# zxdos_trainer.net
KiCad netlist of a schematic drawn in EAGLE
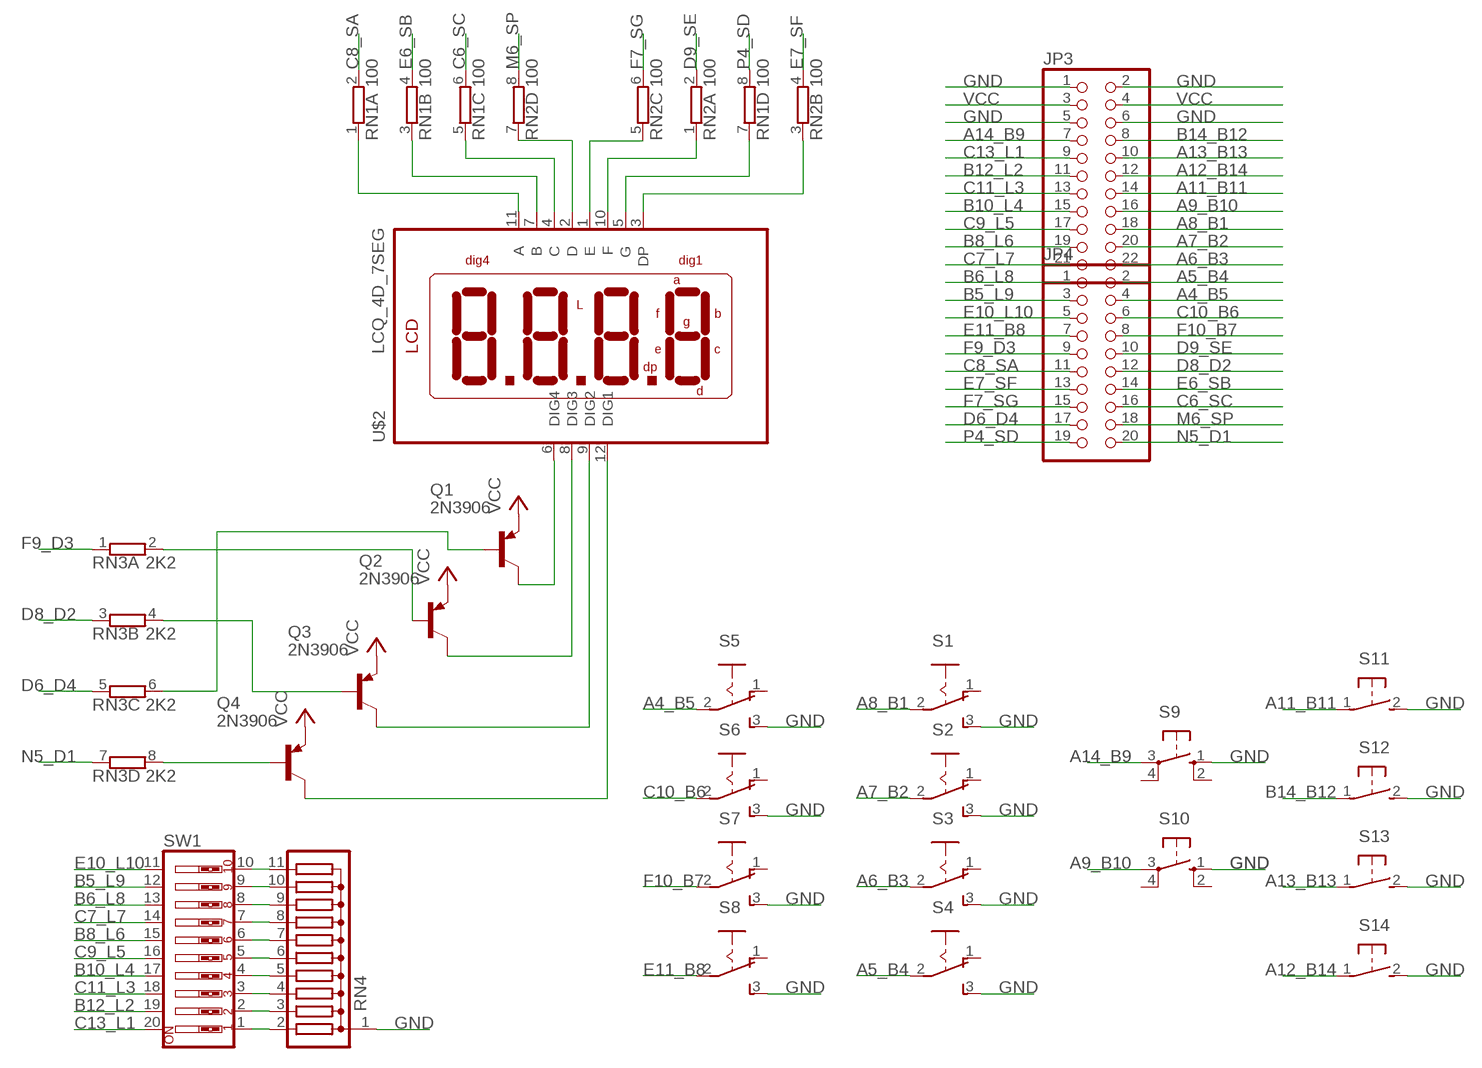
[diagram p0: schematic, sheet 1]

(export (version "E")
  (design (tool "Eeschema 10.0.6"))
  (components
    (comp (ref "JP3")
      (value "PINHD-2X11")
      (footprint "eagle-import:2X11")
      (libsource (lib "eagle-import") (part "PINHD-2X11"))
    )
    (comp (ref "JP4")
      (value "PINHD-2X10")
      (footprint "eagle-import:2X10")
      (libsource (lib "eagle-import") (part "PINHD-2X10"))
    )
    (comp (ref "Q1")
      (value "2N3906")
      (footprint "eagle-import:TO92")
      (libsource (lib "eagle-import") (part "2N3906"))
    )
    (comp (ref "Q2")
      (value "2N3906")
      (footprint "eagle-import:TO92")
      (libsource (lib "eagle-import") (part "2N3906"))
    )
    (comp (ref "Q3")
      (value "2N3906")
      (footprint "eagle-import:TO92")
      (libsource (lib "eagle-import") (part "2N3906"))
    )
    (comp (ref "Q4")
      (value "2N3906")
      (footprint "eagle-import:TO92")
      (libsource (lib "eagle-import") (part "2N3906"))
    )
    (comp (ref "RN1")
      (value "100")
      (footprint "eagle-import:SIL8")
      (libsource (lib "eagle-import") (part "E4R"))
    )
    (comp (ref "RN2")
      (value "100")
      (footprint "eagle-import:SIL8")
      (libsource (lib "eagle-import") (part "E4R"))
    )
    (comp (ref "RN3")
      (value "2K2")
      (footprint "eagle-import:SIL8")
      (libsource (lib "eagle-import") (part "E4R"))
    )
    (comp (ref "RN4")
      (value "G10R")
      (footprint "eagle-import:SIL11")
      (libsource (lib "eagle-import") (part "G10R"))
    )
    (comp (ref "S1")
      (value "M251")
      (footprint "eagle-import:M251")
      (libsource (lib "eagle-import") (part "M251"))
    )
    (comp (ref "S2")
      (value "M251")
      (footprint "eagle-import:M251")
      (libsource (lib "eagle-import") (part "M251"))
    )
    (comp (ref "S3")
      (value "M251")
      (footprint "eagle-import:M251")
      (libsource (lib "eagle-import") (part "M251"))
    )
    (comp (ref "S4")
      (value "M251")
      (footprint "eagle-import:M251")
      (libsource (lib "eagle-import") (part "M251"))
    )
    (comp (ref "S5")
      (value "M251")
      (footprint "eagle-import:M251")
      (libsource (lib "eagle-import") (part "M251"))
    )
    (comp (ref "S6")
      (value "M251")
      (footprint "eagle-import:M251")
      (libsource (lib "eagle-import") (part "M251"))
    )
    (comp (ref "S7")
      (value "M251")
      (footprint "eagle-import:M251")
      (libsource (lib "eagle-import") (part "M251"))
    )
    (comp (ref "S8")
      (value "M251")
      (footprint "eagle-import:M251")
      (libsource (lib "eagle-import") (part "M251"))
    )
    (comp (ref "S9")
      (value "10-XX")
      (footprint "eagle-import:B3F-10XX")
      (fields (field (name "MPN") "B3F-1000"))
      (libsource (lib "eagle-import") (part "10-XX"))
    )
    (comp (ref "S10")
      (value "10-XX")
      (footprint "eagle-import:B3F-10XX")
      (fields (field (name "MPN") "B3F-1000"))
      (libsource (lib "eagle-import") (part "10-XX"))
    )
    (comp (ref "S11")
      (value "31-XX")
      (footprint "eagle-import:B3F-31XX")
      (fields (field (name "MPN") "B3F-3100"))
      (libsource (lib "eagle-import") (part "31-XX"))
    )
    (comp (ref "S12")
      (value "31-XX")
      (footprint "eagle-import:B3F-31XX")
      (fields (field (name "MPN") "B3F-3100"))
      (libsource (lib "eagle-import") (part "31-XX"))
    )
    (comp (ref "S13")
      (value "31-XX")
      (footprint "eagle-import:B3F-31XX")
      (fields (field (name "MPN") "B3F-3100"))
      (libsource (lib "eagle-import") (part "31-XX"))
    )
    (comp (ref "S14")
      (value "31-XX")
      (footprint "eagle-import:B3F-31XX")
      (fields (field (name "MPN") "B3F-3100"))
      (libsource (lib "eagle-import") (part "31-XX"))
    )
    (comp (ref "SW1")
      (value "SW_DIP-10")
      (footprint "eagle-import:EDG-10")
      (libsource (lib "eagle-import") (part "SW_DIP-10"))
    )
    (comp (ref "U$2")
      (value "LCQ_4D_7SEG")
      (footprint "eagle-import:LDQ_4D_7SEG")
      (libsource (lib "eagle-import") (part "LCQ_4D_7SEG"))
    )
  )
  (nets
    (net (code "1") (name "/A4_B5") (class "Default")
      (node (ref "JP4") (pin "4") (pinfunction "4_4") (pintype "passive"))
      (node (ref "S5") (pin "2") (pinfunction "P_2") (pintype "passive"))
    )
    (net (code "2") (name "/A5_B4") (class "Default")
      (node (ref "JP4") (pin "2") (pinfunction "2_2") (pintype "passive"))
      (node (ref "S4") (pin "2") (pinfunction "P_2") (pintype "passive"))
    )
    (net (code "3") (name "/A6_B3") (class "Default")
      (node (ref "JP3") (pin "22") (pinfunction "22_22") (pintype "passive"))
      (node (ref "S3") (pin "2") (pinfunction "P_2") (pintype "passive"))
    )
    (net (code "4") (name "/A7_B2") (class "Default")
      (node (ref "JP3") (pin "20") (pinfunction "20_20") (pintype "passive"))
      (node (ref "S2") (pin "2") (pinfunction "P_2") (pintype "passive"))
    )
    (net (code "5") (name "/A8_B1") (class "Default")
      (node (ref "JP3") (pin "18") (pinfunction "18_18") (pintype "passive"))
      (node (ref "S1") (pin "2") (pinfunction "P_2") (pintype "passive"))
    )
    (net (code "6") (name "/A9_B10") (class "Default")
      (node (ref "JP3") (pin "16") (pinfunction "16_16") (pintype "passive"))
      (node (ref "S10") (pin "3") (pinfunction "P_3") (pintype "passive"))
    )
    (net (code "7") (name "/A11_B11") (class "Default")
      (node (ref "JP3") (pin "14") (pinfunction "14_14") (pintype "passive"))
      (node (ref "S11") (pin "1") (pinfunction "P_1") (pintype "passive"))
    )
    (net (code "8") (name "/A12_B14") (class "Default")
      (node (ref "JP3") (pin "12") (pinfunction "12_12") (pintype "passive"))
      (node (ref "S14") (pin "1") (pinfunction "P_1") (pintype "passive"))
    )
    (net (code "9") (name "/A13_B13") (class "Default")
      (node (ref "JP3") (pin "10") (pinfunction "10_10") (pintype "passive"))
      (node (ref "S13") (pin "1") (pinfunction "P_1") (pintype "passive"))
    )
    (net (code "10") (name "/A14_B9") (class "Default")
      (node (ref "JP3") (pin "7") (pinfunction "7_7") (pintype "passive"))
      (node (ref "S9") (pin "3") (pinfunction "P_3") (pintype "passive"))
    )
    (net (code "11") (name "/B5_L9") (class "Default")
      (node (ref "JP4") (pin "3") (pinfunction "3_3") (pintype "passive"))
      (node (ref "SW1") (pin "12") (pinfunction "12_12") (pintype "passive"))
    )
    (net (code "12") (name "/B6_L8") (class "Default")
      (node (ref "JP4") (pin "1") (pinfunction "1_1") (pintype "passive"))
      (node (ref "SW1") (pin "13") (pinfunction "13_13") (pintype "passive"))
    )
    (net (code "13") (name "/B8_L6") (class "Default")
      (node (ref "JP3") (pin "19") (pinfunction "19_19") (pintype "passive"))
      (node (ref "SW1") (pin "15") (pinfunction "15_15") (pintype "passive"))
    )
    (net (code "14") (name "/B10_L4") (class "Default")
      (node (ref "JP3") (pin "15") (pinfunction "15_15") (pintype "passive"))
      (node (ref "SW1") (pin "17") (pinfunction "17_17") (pintype "passive"))
    )
    (net (code "15") (name "/B12_L2") (class "Default")
      (node (ref "JP3") (pin "11") (pinfunction "11_11") (pintype "passive"))
      (node (ref "SW1") (pin "19") (pinfunction "19_19") (pintype "passive"))
    )
    (net (code "16") (name "/B14_B12") (class "Default")
      (node (ref "JP3") (pin "8") (pinfunction "8_8") (pintype "passive"))
      (node (ref "S12") (pin "1") (pinfunction "P_1") (pintype "passive"))
    )
    (net (code "17") (name "/C6_SC") (class "Default")
      (node (ref "JP4") (pin "16") (pinfunction "16_16") (pintype "passive"))
      (node (ref "RN1") (pin "6") (pinfunction "2_6") (pintype "passive"))
    )
    (net (code "18") (name "/C7_L7") (class "Default")
      (node (ref "JP3") (pin "21") (pinfunction "21_21") (pintype "passive"))
      (node (ref "SW1") (pin "14") (pinfunction "14_14") (pintype "passive"))
    )
    (net (code "19") (name "/C8_SA") (class "Default")
      (node (ref "JP4") (pin "11") (pinfunction "11_11") (pintype "passive"))
      (node (ref "RN1") (pin "2") (pinfunction "2_2") (pintype "passive"))
    )
    (net (code "20") (name "/C9_L5") (class "Default")
      (node (ref "JP3") (pin "17") (pinfunction "17_17") (pintype "passive"))
      (node (ref "SW1") (pin "16") (pinfunction "16_16") (pintype "passive"))
    )
    (net (code "21") (name "/C10_B6") (class "Default")
      (node (ref "JP4") (pin "6") (pinfunction "6_6") (pintype "passive"))
      (node (ref "S6") (pin "2") (pinfunction "P_2") (pintype "passive"))
    )
    (net (code "22") (name "/C11_L3") (class "Default")
      (node (ref "JP3") (pin "13") (pinfunction "13_13") (pintype "passive"))
      (node (ref "SW1") (pin "18") (pinfunction "18_18") (pintype "passive"))
    )
    (net (code "23") (name "/C13_L1") (class "Default")
      (node (ref "JP3") (pin "9") (pinfunction "9_9") (pintype "passive"))
      (node (ref "SW1") (pin "20") (pinfunction "20_20") (pintype "passive"))
    )
    (net (code "24") (name "/D6_D4") (class "Default")
      (node (ref "JP4") (pin "17") (pinfunction "17_17") (pintype "passive"))
      (node (ref "RN3") (pin "5") (pinfunction "1_5") (pintype "passive"))
    )
    (net (code "25") (name "/D8_D2") (class "Default")
      (node (ref "JP4") (pin "12") (pinfunction "12_12") (pintype "passive"))
      (node (ref "RN3") (pin "3") (pinfunction "1_3") (pintype "passive"))
    )
    (net (code "26") (name "/D9_SE") (class "Default")
      (node (ref "JP4") (pin "10") (pinfunction "10_10") (pintype "passive"))
      (node (ref "RN2") (pin "2") (pinfunction "2_2") (pintype "passive"))
    )
    (net (code "27") (name "/E6_SB") (class "Default")
      (node (ref "JP4") (pin "14") (pinfunction "14_14") (pintype "passive"))
      (node (ref "RN1") (pin "4") (pinfunction "2_4") (pintype "passive"))
    )
    (net (code "28") (name "/E7_SF") (class "Default")
      (node (ref "JP4") (pin "13") (pinfunction "13_13") (pintype "passive"))
      (node (ref "RN2") (pin "4") (pinfunction "2_4") (pintype "passive"))
    )
    (net (code "29") (name "/E10_L10") (class "Default")
      (node (ref "JP4") (pin "5") (pinfunction "5_5") (pintype "passive"))
      (node (ref "SW1") (pin "11") (pinfunction "11_11") (pintype "passive"))
    )
    (net (code "30") (name "/E11_B8") (class "Default")
      (node (ref "JP4") (pin "7") (pinfunction "7_7") (pintype "passive"))
      (node (ref "S8") (pin "2") (pinfunction "P_2") (pintype "passive"))
    )
    (net (code "31") (name "/F7_SG") (class "Default")
      (node (ref "JP4") (pin "15") (pinfunction "15_15") (pintype "passive"))
      (node (ref "RN2") (pin "6") (pinfunction "2_6") (pintype "passive"))
    )
    (net (code "32") (name "/F9_D3") (class "Default")
      (node (ref "JP4") (pin "9") (pinfunction "9_9") (pintype "passive"))
      (node (ref "RN3") (pin "1") (pinfunction "1_1") (pintype "passive"))
    )
    (net (code "33") (name "/F10_B7") (class "Default")
      (node (ref "JP4") (pin "8") (pinfunction "8_8") (pintype "passive"))
      (node (ref "S7") (pin "2") (pinfunction "P_2") (pintype "passive"))
    )
    (net (code "34") (name "/GND") (class "Default")
      (node (ref "JP3") (pin "1") (pinfunction "1_1") (pintype "passive"))
      (node (ref "JP3") (pin "2") (pinfunction "2_2") (pintype "passive"))
      (node (ref "JP3") (pin "5") (pinfunction "5_5") (pintype "passive"))
      (node (ref "JP3") (pin "6") (pinfunction "6_6") (pintype "passive"))
      (node (ref "RN4") (pin "1") (pinfunction "1_1") (pintype "passive"))
      (node (ref "S1") (pin "3") (pinfunction "S_3") (pintype "passive"))
      (node (ref "S10") (pin "1") (pinfunction "S_1") (pintype "passive"))
      (node (ref "S11") (pin "2") (pinfunction "S_2") (pintype "passive"))
      (node (ref "S12") (pin "2") (pinfunction "S_2") (pintype "passive"))
      (node (ref "S13") (pin "2") (pinfunction "S_2") (pintype "passive"))
      (node (ref "S14") (pin "2") (pinfunction "S_2") (pintype "passive"))
      (node (ref "S2") (pin "3") (pinfunction "S_3") (pintype "passive"))
      (node (ref "S3") (pin "3") (pinfunction "S_3") (pintype "passive"))
      (node (ref "S4") (pin "3") (pinfunction "S_3") (pintype "passive"))
      (node (ref "S5") (pin "3") (pinfunction "S_3") (pintype "passive"))
      (node (ref "S6") (pin "3") (pinfunction "S_3") (pintype "passive"))
      (node (ref "S7") (pin "3") (pinfunction "S_3") (pintype "passive"))
      (node (ref "S8") (pin "3") (pinfunction "S_3") (pintype "passive"))
      (node (ref "S9") (pin "1") (pinfunction "S_1") (pintype "passive"))
    )
    (net (code "35") (name "/M6_SP") (class "Default")
      (node (ref "JP4") (pin "18") (pinfunction "18_18") (pintype "passive"))
      (node (ref "RN2") (pin "8") (pinfunction "2_8") (pintype "passive"))
    )
    (net (code "36") (name "/N5_D1") (class "Default")
      (node (ref "JP4") (pin "20") (pinfunction "20_20") (pintype "passive"))
      (node (ref "RN3") (pin "7") (pinfunction "1_7") (pintype "passive"))
    )
    (net (code "37") (name "/P4_SD") (class "Default")
      (node (ref "JP4") (pin "19") (pinfunction "19_19") (pintype "passive"))
      (node (ref "RN1") (pin "8") (pinfunction "2_8") (pintype "passive"))
    )
    (net (code "38") (name "Net-(Q1-B)") (class "Default")
      (node (ref "Q1") (pin "2") (pinfunction "B_2") (pintype "passive"))
      (node (ref "RN3") (pin "6") (pinfunction "2_6") (pintype "passive"))
    )
    (net (code "39") (name "Net-(Q1-C)") (class "Default")
      (node (ref "Q1") (pin "1") (pinfunction "C_1") (pintype "passive"))
      (node (ref "U$2") (pin "6") (pinfunction "DIG4_6") (pintype "input"))
    )
    (net (code "40") (name "Net-(Q2-B)") (class "Default")
      (node (ref "Q2") (pin "2") (pinfunction "B_2") (pintype "passive"))
      (node (ref "RN3") (pin "2") (pinfunction "2_2") (pintype "passive"))
    )
    (net (code "41") (name "Net-(Q2-C)") (class "Default")
      (node (ref "Q2") (pin "1") (pinfunction "C_1") (pintype "passive"))
      (node (ref "U$2") (pin "8") (pinfunction "DIG3_8") (pintype "input"))
    )
    (net (code "42") (name "Net-(Q3-B)") (class "Default")
      (node (ref "Q3") (pin "2") (pinfunction "B_2") (pintype "passive"))
      (node (ref "RN3") (pin "4") (pinfunction "2_4") (pintype "passive"))
    )
    (net (code "43") (name "Net-(Q3-C)") (class "Default")
      (node (ref "Q3") (pin "1") (pinfunction "C_1") (pintype "passive"))
      (node (ref "U$2") (pin "9") (pinfunction "DIG2_9") (pintype "input"))
    )
    (net (code "44") (name "Net-(Q4-B)") (class "Default")
      (node (ref "Q4") (pin "2") (pinfunction "B_2") (pintype "passive"))
      (node (ref "RN3") (pin "8") (pinfunction "2_8") (pintype "passive"))
    )
    (net (code "45") (name "Net-(Q4-C)") (class "Default")
      (node (ref "Q4") (pin "1") (pinfunction "C_1") (pintype "passive"))
      (node (ref "U$2") (pin "12") (pinfunction "DIG1_12") (pintype "input"))
    )
    (net (code "46") (name "Net-(RN1B-1)") (class "Default")
      (node (ref "RN1") (pin "3") (pinfunction "1_3") (pintype "passive"))
      (node (ref "U$2") (pin "7") (pinfunction "B_7") (pintype "input"))
    )
    (net (code "47") (name "Net-(RN1C-1)") (class "Default")
      (node (ref "RN1") (pin "5") (pinfunction "1_5") (pintype "passive"))
      (node (ref "U$2") (pin "4") (pinfunction "C_4") (pintype "input"))
    )
    (net (code "48") (name "Net-(RN1D-1)") (class "Default")
      (node (ref "RN1") (pin "7") (pinfunction "1_7") (pintype "passive"))
      (node (ref "U$2") (pin "5") (pinfunction "G_5") (pintype "input"))
    )
    (net (code "49") (name "Net-(RN2B-1)") (class "Default")
      (node (ref "RN2") (pin "3") (pinfunction "1_3") (pintype "passive"))
      (node (ref "U$2") (pin "3") (pinfunction "DP_3") (pintype "input"))
    )
    (net (code "50") (name "Net-(RN2C-1)") (class "Default")
      (node (ref "RN2") (pin "5") (pinfunction "1_5") (pintype "passive"))
      (node (ref "U$2") (pin "1") (pinfunction "E_1") (pintype "input"))
    )
    (net (code "51") (name "Net-(RN2D-1)") (class "Default")
      (node (ref "RN2") (pin "7") (pinfunction "1_7") (pintype "passive"))
      (node (ref "U$2") (pin "2") (pinfunction "D_2") (pintype "input"))
    )
    (net (code "52") (name "Net-(RN4-Pad2)") (class "Default")
      (node (ref "RN4") (pin "2") (pinfunction "2_2") (pintype "passive"))
      (node (ref "SW1") (pin "1") (pinfunction "1_1") (pintype "passive"))
    )
    (net (code "53") (name "Net-(RN4-Pad3)") (class "Default")
      (node (ref "RN4") (pin "3") (pinfunction "3_3") (pintype "passive"))
      (node (ref "SW1") (pin "2") (pinfunction "2_2") (pintype "passive"))
    )
    (net (code "54") (name "Net-(RN4-Pad4)") (class "Default")
      (node (ref "RN4") (pin "4") (pinfunction "4_4") (pintype "passive"))
      (node (ref "SW1") (pin "3") (pinfunction "3_3") (pintype "passive"))
    )
    (net (code "55") (name "Net-(RN4-Pad5)") (class "Default")
      (node (ref "RN4") (pin "5") (pinfunction "5_5") (pintype "passive"))
      (node (ref "SW1") (pin "4") (pinfunction "4_4") (pintype "passive"))
    )
    (net (code "56") (name "Net-(RN4-Pad6)") (class "Default")
      (node (ref "RN4") (pin "6") (pinfunction "6_6") (pintype "passive"))
      (node (ref "SW1") (pin "5") (pinfunction "5_5") (pintype "passive"))
    )
    (net (code "57") (name "Net-(RN4-Pad7)") (class "Default")
      (node (ref "RN4") (pin "7") (pinfunction "7_7") (pintype "passive"))
      (node (ref "SW1") (pin "6") (pinfunction "6_6") (pintype "passive"))
    )
    (net (code "58") (name "Net-(RN4-Pad8)") (class "Default")
      (node (ref "RN4") (pin "8") (pinfunction "8_8") (pintype "passive"))
      (node (ref "SW1") (pin "7") (pinfunction "7_7") (pintype "passive"))
    )
    (net (code "59") (name "Net-(RN4-Pad9)") (class "Default")
      (node (ref "RN4") (pin "9") (pinfunction "9_9") (pintype "passive"))
      (node (ref "SW1") (pin "8") (pinfunction "8_8") (pintype "passive"))
    )
    (net (code "60") (name "Net-(RN4-Pad10)") (class "Default")
      (node (ref "RN4") (pin "10") (pinfunction "10_10") (pintype "passive"))
      (node (ref "SW1") (pin "9") (pinfunction "9_9") (pintype "passive"))
    )
    (net (code "61") (name "Net-(RN4-Pad11)") (class "Default")
      (node (ref "RN4") (pin "11") (pinfunction "11_11") (pintype "passive"))
      (node (ref "SW1") (pin "10") (pinfunction "10_10") (pintype "passive"))
    )
    (net (code "62") (name "Net-(U$2-A)") (class "Default")
      (node (ref "RN1") (pin "1") (pinfunction "1_1") (pintype "passive"))
      (node (ref "U$2") (pin "11") (pinfunction "A_11") (pintype "input"))
    )
    (net (code "63") (name "Net-(U$2-F)") (class "Default")
      (node (ref "RN2") (pin "1") (pinfunction "1_1") (pintype "passive"))
      (node (ref "U$2") (pin "10") (pinfunction "F_10") (pintype "input"))
    )
    (net (code "64") (name "VCC") (class "Default")
      (node (ref "JP3") (pin "3") (pinfunction "3_3") (pintype "passive"))
      (node (ref "JP3") (pin "4") (pinfunction "4_4") (pintype "passive"))
      (node (ref "Q1") (pin "3") (pinfunction "E_3") (pintype "passive"))
      (node (ref "Q2") (pin "3") (pinfunction "E_3") (pintype "passive"))
      (node (ref "Q3") (pin "3") (pinfunction "E_3") (pintype "passive"))
      (node (ref "Q4") (pin "3") (pinfunction "E_3") (pintype "passive"))
    )
    (net (code "65") (name "unconnected-(S1-O-Pad1)") (class "Default")
      (node (ref "S1") (pin "1") (pinfunction "O_1") (pintype "passive"))
    )
    (net (code "66") (name "unconnected-(S2-O-Pad1)") (class "Default")
      (node (ref "S2") (pin "1") (pinfunction "O_1") (pintype "passive"))
    )
    (net (code "67") (name "unconnected-(S3-O-Pad1)") (class "Default")
      (node (ref "S3") (pin "1") (pinfunction "O_1") (pintype "passive"))
    )
    (net (code "68") (name "unconnected-(S4-O-Pad1)") (class "Default")
      (node (ref "S4") (pin "1") (pinfunction "O_1") (pintype "passive"))
    )
    (net (code "69") (name "unconnected-(S5-O-Pad1)") (class "Default")
      (node (ref "S5") (pin "1") (pinfunction "O_1") (pintype "passive"))
    )
    (net (code "70") (name "unconnected-(S6-O-Pad1)") (class "Default")
      (node (ref "S6") (pin "1") (pinfunction "O_1") (pintype "passive"))
    )
    (net (code "71") (name "unconnected-(S7-O-Pad1)") (class "Default")
      (node (ref "S7") (pin "1") (pinfunction "O_1") (pintype "passive"))
    )
    (net (code "72") (name "unconnected-(S8-O-Pad1)") (class "Default")
      (node (ref "S8") (pin "1") (pinfunction "O_1") (pintype "passive"))
    )
    (net (code "73") (name "unconnected-(S9-P1-Pad4)") (class "Default")
      (node (ref "S9") (pin "4") (pinfunction "P1_4") (pintype "passive"))
    )
    (net (code "74") (name "unconnected-(S9-S1-Pad2)") (class "Default")
      (node (ref "S9") (pin "2") (pinfunction "S1_2") (pintype "passive"))
    )
    (net (code "75") (name "unconnected-(S10-P1-Pad4)") (class "Default")
      (node (ref "S10") (pin "4") (pinfunction "P1_4") (pintype "passive"))
    )
    (net (code "76") (name "unconnected-(S10-S1-Pad2)") (class "Default")
      (node (ref "S10") (pin "2") (pinfunction "S1_2") (pintype "passive"))
    )
  )
)
